# 01_SYSTEM_POWER.net
KiCad netlist of a schematic drawn in Altium Designer
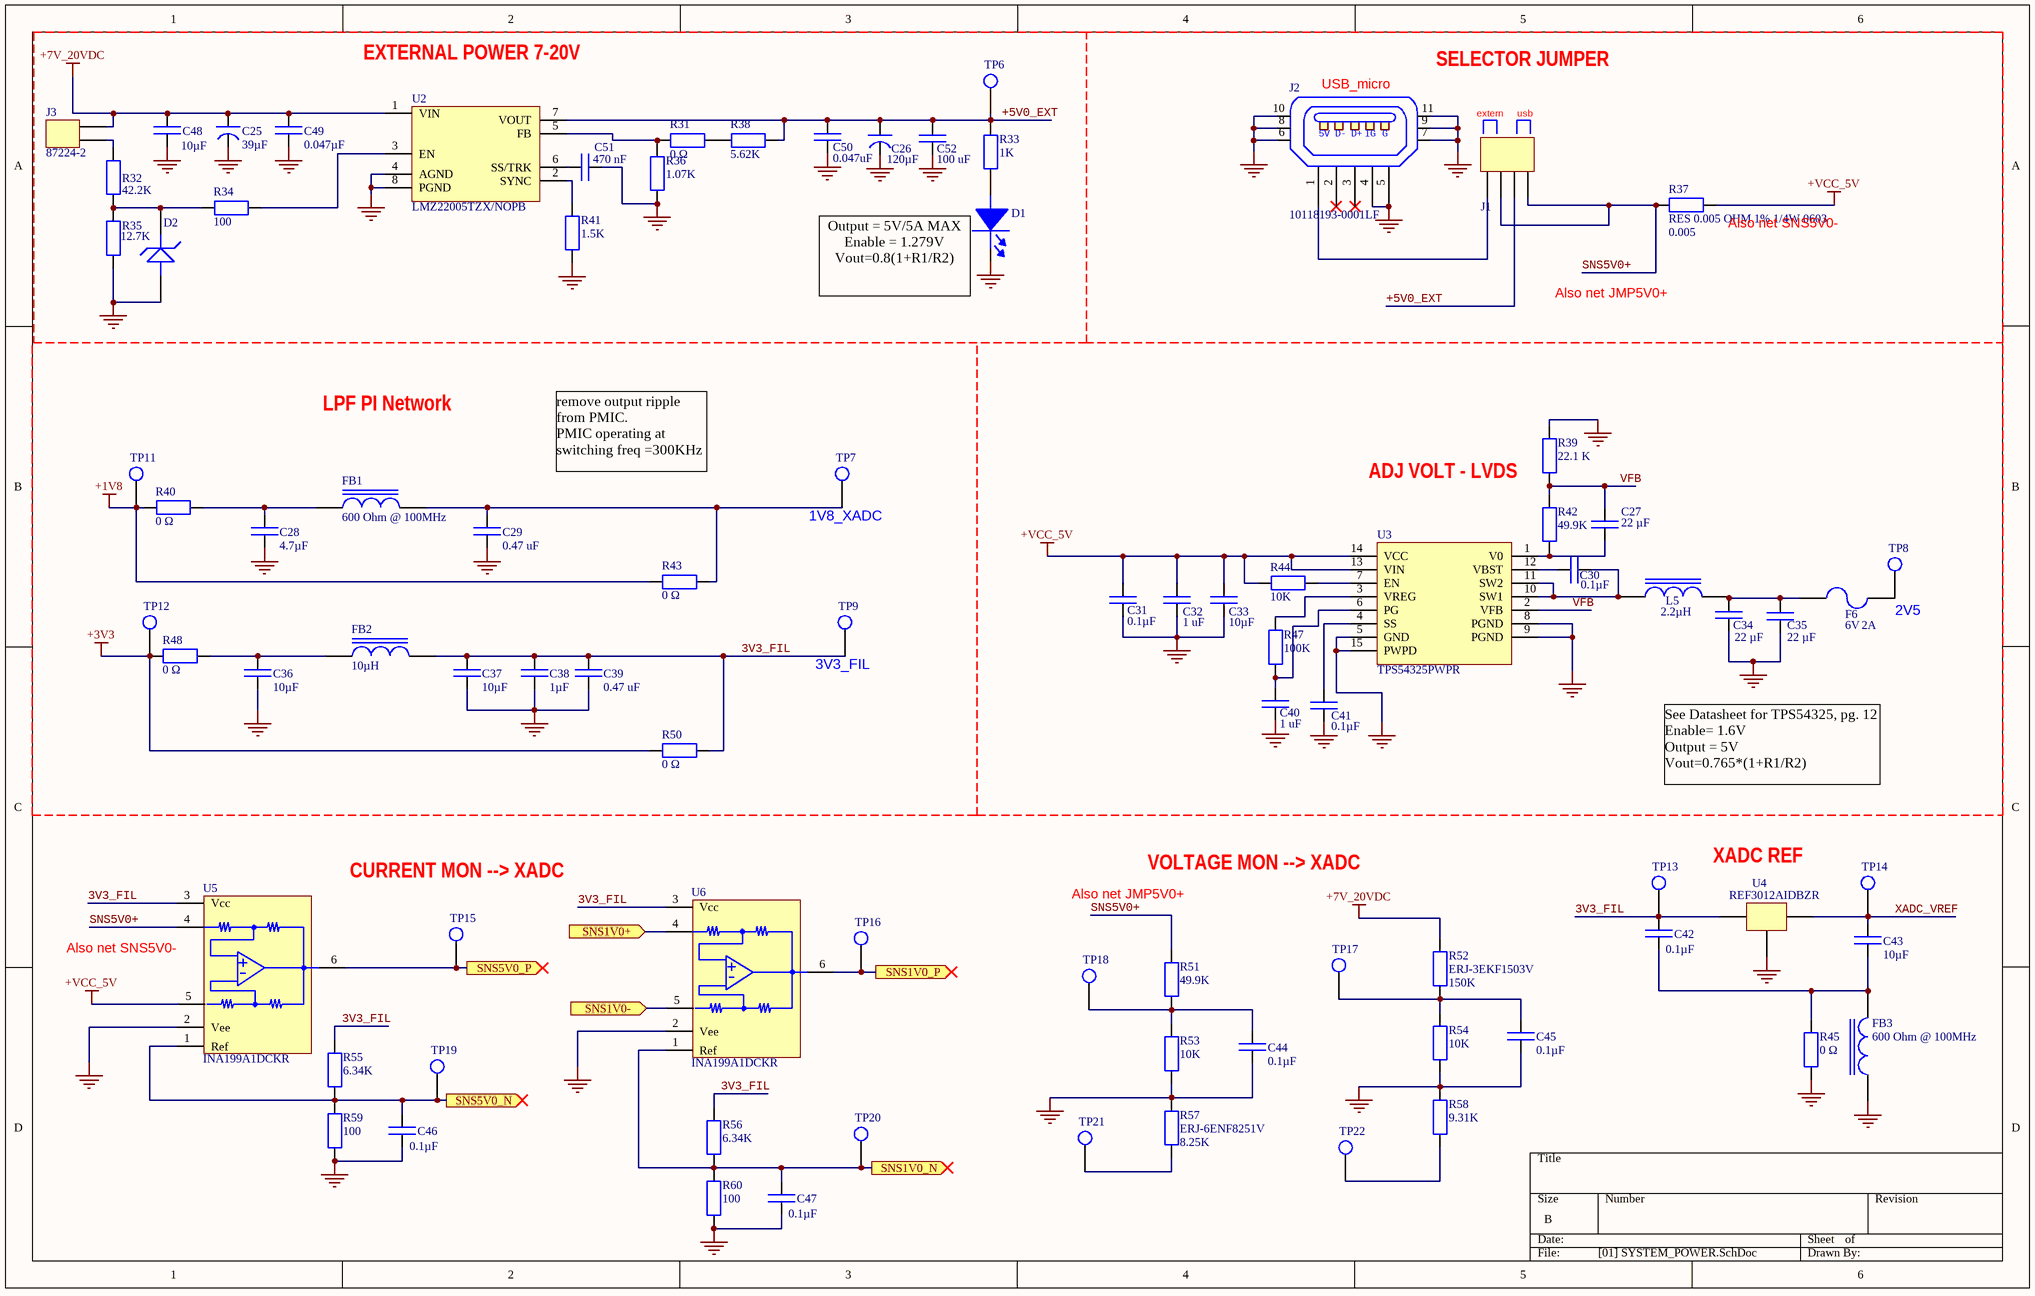
[diagram p0: [01] SYSTEM_POWER.SchDoc]

(export (version "E")
  (design (tool "Eeschema 10.0.6"))
  (components
    (comp (ref "C25")
      (value "35SVPF39M")
      (footprint "Radial E7")
      (description "CAP ALUM POLY 39UF 20% 35V SMD")
      (fields
        (field (name "MANUFACTURER") "Panasonic")
        (field (name "TOLERANCE") "±20%")
        (field (name "CAPACITANCE") "39µF")
      )
      (libsource (lib "Super_Hornet") (part "35SVPF39M"))
    )
    (comp (ref "C26")
      (value "20SVPF120M")
      (footprint "Radial C6")
      (description "CAP ALUM POLY 120UF 20% 20V SMD")
      (fields
        (field (name "MANUFACTURER") "Panasonic")
        (field (name "TOLERANCE") "±20%")
        (field (name "CAPACITANCE") "120µF")
      )
      (libsource (lib "Honey_Badger") (part "20SVPF120M"))
    )
    (comp (ref "C27")
      (value "12063D226KAT2A")
      (footprint "C1206")
      (description "CAP CER 22UF 25V X5R 1206")
      (fields (field (name "MANUFACTURER") "Kyocera AVX") (field (name "CAPACITANCE") "22 µF"))
      (libsource (lib "Honey_Badger") (part "12063D226KAT2A"))
    )
    (comp (ref "C28")
      (value "C2012X5R1C475K060AC")
      (footprint "C0805_1")
      (description "CAP CER 4.7UF 16V X5R 0805")
      (fields
        (field (name "MANUFACTURER") "TDK")
        (field (name "TOLERANCE") "±10%")
        (field (name "CAPACITANCE") "4.7µF")
      )
      (libsource (lib "Honey_Badger") (part "C2012X5R1C475K060AC"))
    )
    (comp (ref "C29")
      (value "GRM188R70J474KA01D")
      (footprint "C0603_1")
      (description "CAP CER 0.47UF 6.3V X7R 0603")
      (fields
        (field (name "MANUFACTURER") "Murata")
        (field (name "TOLERANCE") "10 %")
        (field (name "CAPACITANCE") "0.47 uF")
      )
      (libsource (lib "Honey_Badger") (part "GRM188R70J474KA01D"))
    )
    (comp (ref "C30")
      (value "CC0402KRX7R6BB104")
      (footprint "R0402")
      (description "0402 0.1 uF 10 V ±10 % Tolerance X7R SMT Multilayer Ceramic Capacitor")
      (fields
        (field (name "MANUFACTURER") "Yageo")
        (field (name "TOLERANCE") "±10%")
        (field (name "CAPACITANCE") "0.1µF")
      )
      (libsource (lib "Honey_Badger") (part "CC0402KRX7R6BB104"))
    )
    (comp (ref "C31")
      (value "CC0402KRX7R6BB104")
      (footprint "R0402")
      (description "0402 0.1 uF 10 V ±10 % Tolerance X7R SMT Multilayer Ceramic Capacitor")
      (fields
        (field (name "MANUFACTURER") "Yageo")
        (field (name "TOLERANCE") "±10%")
        (field (name "CAPACITANCE") "0.1µF")
      )
      (libsource (lib "Honey_Badger") (part "CC0402KRX7R6BB104"))
    )
    (comp (ref "C32")
      (value "C0603C105K8RACTU")
      (footprint "C0603_1")
      (description "CAP CER 1UF 10V X7R 0603")
      (fields
        (field (name "MANUFACTURER") "KEMET")
        (field (name "TOLERANCE") "10 %")
        (field (name "CAPACITANCE") "1 uF")
      )
      (libsource (lib "Honey_Badger") (part "C0603C105K8RACTU"))
    )
    (comp (ref "C33")
      (value "C3216X5R1C106M160AA")
      (footprint "C1206")
      (description "CAP CER 10UF 16V X5R 1206")
      (fields
        (field (name "MANUFACTURER") "TDK")
        (field (name "PCN PART NUMBER") "MLCC Part Number Change 30/Nov/2012")
        (field (name "CAPACITANCE") "10µF")
      )
      (libsource (lib "Honey_Badger") (part "C3216X5R1C106M160AA"))
    )
    (comp (ref "C34")
      (value "12063D226KAT2A")
      (footprint "C1206")
      (description "CAP CER 22UF 25V X5R 1206")
      (fields (field (name "MANUFACTURER") "Kyocera AVX") (field (name "CAPACITANCE") "22 µF"))
      (libsource (lib "Honey_Badger") (part "12063D226KAT2A"))
    )
    (comp (ref "C35")
      (value "12063D226KAT2A")
      (footprint "C1206")
      (description "CAP CER 22UF 25V X5R 1206")
      (fields (field (name "MANUFACTURER") "Kyocera AVX") (field (name "CAPACITANCE") "22 µF"))
      (libsource (lib "Honey_Badger") (part "12063D226KAT2A"))
    )
    (comp (ref "C36")
      (value "C3216X5R1C106M160AA")
      (footprint "C1206")
      (description "CAP CER 10UF 16V X5R 1206")
      (fields
        (field (name "MANUFACTURER") "TDK")
        (field (name "PCN PART NUMBER") "MLCC Part Number Change 30/Nov/2012")
        (field (name "CAPACITANCE") "10µF")
      )
      (libsource (lib "Honey_Badger") (part "C3216X5R1C106M160AA"))
    )
    (comp (ref "C37")
      (value "C3216X5R1C106M160AA")
      (footprint "C1206")
      (description "CAP CER 10UF 16V X5R 1206")
      (fields
        (field (name "MANUFACTURER") "TDK")
        (field (name "PCN PART NUMBER") "MLCC Part Number Change 30/Nov/2012")
        (field (name "CAPACITANCE") "10µF")
      )
      (libsource (lib "Honey_Badger") (part "C3216X5R1C106M160AA"))
    )
    (comp (ref "C38")
      (value "C3216X7R1H105K160AE")
      (footprint "C1206")
      (description "CAP CER 1UF 50V X7R 1206")
      (fields
        (field (name "MANUFACTURER") "TDK")
        (field (name "PCN PART NUMBER") "MLCC Part Number Change 30/Nov/2012")
        (field (name "CAPACITANCE") "1µF")
      )
      (libsource (lib "Honey_Badger") (part "C3216X7R1H105K160AE"))
    )
    (comp (ref "C39")
      (value "GRM188R70J474KA01D")
      (footprint "C0603_1")
      (description "CAP CER 0.47UF 6.3V X7R 0603")
      (fields
        (field (name "MANUFACTURER") "Murata")
        (field (name "TOLERANCE") "10 %")
        (field (name "CAPACITANCE") "0.47 uF")
      )
      (libsource (lib "Honey_Badger") (part "GRM188R70J474KA01D"))
    )
    (comp (ref "C40")
      (value "C0603C105K8RACTU")
      (footprint "C0603_1")
      (description "CAP CER 1UF 10V X7R 0603")
      (fields
        (field (name "MANUFACTURER") "KEMET")
        (field (name "TOLERANCE") "10 %")
        (field (name "CAPACITANCE") "1 uF")
      )
      (libsource (lib "Honey_Badger") (part "C0603C105K8RACTU"))
    )
    (comp (ref "C41")
      (value "CC0402KRX7R6BB104")
      (footprint "R0402")
      (description "0402 0.1 uF 10 V ±10 % Tolerance X7R SMT Multilayer Ceramic Capacitor")
      (fields
        (field (name "MANUFACTURER") "Yageo")
        (field (name "TOLERANCE") "±10%")
        (field (name "CAPACITANCE") "0.1µF")
      )
      (libsource (lib "Honey_Badger") (part "CC0402KRX7R6BB104"))
    )
    (comp (ref "C42")
      (value "CC0402KRX7R6BB104")
      (footprint "R0402")
      (description "CAP CER 0.1UF 10V X7R 0402")
      (fields
        (field (name "MANUFACTURER") "Yageo")
        (field (name "TOLERANCE") "±10%")
        (field (name "CAPACITANCE") "0.1µF")
      )
      (libsource (lib "Honey_Badger") (part "CC0402KRX7R6BB104"))
    )
    (comp (ref "C43")
      (value "C3216X5R1C106M160AA")
      (footprint "C1206")
      (description "CAP CER 10UF 16V X5R 1206")
      (fields
        (field (name "MANUFACTURER") "TDK")
        (field (name "PCN PART NUMBER") "MLCC Part Number Change 30/Nov/2012")
        (field (name "CAPACITANCE") "10µF")
      )
      (libsource (lib "Honey_Badger") (part "C3216X5R1C106M160AA"))
    )
    (comp (ref "C44")
      (value "CC0402KRX7R6BB104")
      (footprint "R0402")
      (description "CAP CER 0.1UF 10V X7R 0402")
      (fields
        (field (name "MANUFACTURER") "Yageo")
        (field (name "TOLERANCE") "±10%")
        (field (name "CAPACITANCE") "0.1µF")
      )
      (libsource (lib "Honey_Badger") (part "CC0402KRX7R6BB104"))
    )
    (comp (ref "C45")
      (value "CC0402KRX7R6BB104")
      (footprint "R0402")
      (description "CAP CER 0.1UF 10V X7R 0402")
      (fields
        (field (name "MANUFACTURER") "Yageo")
        (field (name "TOLERANCE") "±10%")
        (field (name "CAPACITANCE") "0.1µF")
      )
      (libsource (lib "Honey_Badger") (part "CC0402KRX7R6BB104"))
    )
    (comp (ref "C46")
      (value "CC0402KRX7R6BB104")
      (footprint "R0402")
      (description "CAP CER 0.1UF 10V X7R 0402")
      (fields
        (field (name "MANUFACTURER") "Yageo")
        (field (name "TOLERANCE") "±10%")
        (field (name "CAPACITANCE") "0.1µF")
      )
      (libsource (lib "Honey_Badger") (part "CC0402KRX7R6BB104"))
    )
    (comp (ref "C47")
      (value "CC0402KRX7R6BB104")
      (footprint "R0402")
      (description "CAP CER 0.1UF 10V X7R 0402")
      (fields
        (field (name "MANUFACTURER") "Yageo")
        (field (name "TOLERANCE") "±10%")
        (field (name "CAPACITANCE") "0.1µF")
      )
      (libsource (lib "Honey_Badger") (part "CC0402KRX7R6BB104"))
    )
    (comp (ref "C48")
      (value "GRM188R6YA106MA73D")
      (footprint "C0603_1")
      (description "CAP CER 10UF 35V X5R 0603")
      (fields
        (field (name "MANUFACTURER") "Murata")
        (field (name "CAPACITANCE") "10µF")
        (field (name "TOLERANCE") "±20%")
      )
      (libsource (lib "Super_Hornet") (part "GRM188R6YA106MA73D"))
    )
    (comp (ref "C49")
      (value "GMK107BJ473KAHT")
      (footprint "C0603_1")
      (description "CAP CER 0.047UF 35V X5R 0603")
      (fields
        (field (name "MANUFACTURER") "Taiyo Yuden")
        (field (name "TOLERANCE") "±10%")
        (field (name "MINIMUM QUANTITY") "0.047µF")
      )
      (libsource (lib "Super_Hornet") (part "GMK107BJ473KAHT"))
    )
    (comp (ref "C50")
      (value "C0603C473K8RAC7867")
      (footprint "R0603")
      (description "CAP CER 0.047UF 10V X7R 0603")
      (fields
        (field (name "MANUFACTURER") "KEMET")
        (field (name "VOLTAGE") "10 Vdc")
        (field (name "CAPACITANCE VALUE") "0.047uF")
      )
      (libsource (lib "Super_Hornet") (part "C0603C473K8RAC7867"))
    )
    (comp (ref "C51")
      (value "0805YC474KAT2A")
      (footprint "C0805_1")
      (description "CAP CER 0.47UF 16V X7R 0805")
      (fields (field (name "MANUFACTURER") "Kyocera AVX") (field (name "CAPACITANCE") "470 nF"))
      (libsource (lib "Super_Hornet") (part "0805YC474KAT2A"))
    )
    (comp (ref "C52")
      (value "GRM31CR60J107ME39K")
      (footprint "C1206")
      (description "CAP CER 100UF 6.3V X5R 1206")
      (fields
        (field (name "MANUFACTURER") "Murata")
        (field (name "VOLTAGE") "6.3 Vdc")
        (field (name "CAPACITANCE VALUE") "100 uF")
      )
      (libsource (lib "Super_Hornet") (part "GRM31CR60J107ME39K"))
    )
    (comp (ref "D1")
      (value "SML-LXFP0603USBCTR")
      (footprint "LED-0603-BLUE")
      (description "LED BLUE CLEAR 0603 SMD")
      (fields (field (name "MANUFACTURER") "Lumex"))
      (libsource (lib "Honey_Badger") (part "SML-LXFP0603USBCTR"))
    )
    (comp (ref "D2")
      (value "MMSZ5231BS-7-F")
      (footprint "SOD-323_R1")
      (description "DIODE ZENER 5.1V 200MW SOD323")
      (fields (field (name "MANUFACTURER") "Diodes"))
      (libsource (lib "Super_Hornet") (part "MMSZ5231BS-7-F"))
    )
    (comp (ref "F6")
      (value "MF-NSML200-2")
      (footprint "C1206 - PTC")
      (description "PTC FUSE 2A HOLD 4ATRIP 6V 50A 0.8W 1s")
      (fields
        (field (name "MANUFACTURER") "Bourns")
        (field (name "VOLTAGE - MAX") "6V")
        (field (name "CURRENT - HOLD (IH) (MAX)") "2A")
      )
      (libsource (lib "Honey_Badger") (part "MF-NSML200-2"))
    )
    (comp (ref "FB1")
      (value "FERRITE BEAD 600 OHM 0805 1LN")
      (footprint "R0805")
      (fields
        (field (name "MANUFACTURER") "Laird")
        (field (name "MANUFACTURER PART NUMBER") "HZ0805E601R-10")
        (field (name "IMPEDANCE @ FREQUENCY") "600 Ohm @ 100MHz")
      )
      (libsource (lib "Honey_Badger") (part "HZ0805E601R-10"))
    )
    (comp (ref "FB2")
      (value "MLZ2012N100LT000")
      (footprint "R0805")
      (description "IND 10UH 500MA 300 MOHM")
      (fields
        (field (name "MANUFACTURER") "TDK")
        (field (name "TOLERANCE") "±20%")
        (field (name "INDUCTANCE") "10µH")
      )
      (libsource (lib "Honey_Badger") (part "MLZ2012N100LT000"))
    )
    (comp (ref "FB3")
      (value "FERRITE BEAD 600 OHM 0805 1LN")
      (footprint "R0805")
      (fields
        (field (name "MANUFACTURER") "Laird")
        (field (name "MANUFACTURER PART NUMBER") "HZ0805E601R-10")
        (field (name "IMPEDANCE @ FREQUENCY") "600 Ohm @ 100MHz")
      )
      (libsource (lib "Honey_Badger") (part "HZ0805E601R-10"))
    )
    (comp (ref "J1")
      (value "PRPC004SAAN-RC")
      (footprint "HDR_MALE_1x4_2.54mm")
      (description "CONN HEADER VERT 4POS 2.54MM")
      (fields (field (name "MANUFACTURER") "Sullins"))
      (libsource (lib "Super_Hornet") (part "PRPC004SAAN-RC"))
    )
    (comp (ref "J2")
      (value "10118193-0001LF")
      (footprint "USB_MICRO - duplicate")
      (description "USB - micro B USB 2.0 Receptacle Connector 5 Position Surface Mount, Right Angle, Horizontal")
      (fields (field (name "MANUFACTURER") "Amphenol FCI"))
      (libsource (lib "Super_Hornet") (part "10118193-0001LF_1"))
    )
    (comp (ref "J3")
      (value "87224-2")
      (footprint "HDR_MALE_1x2_2.54mm")
      (description "CONN HEADER VERT 2POS 2.54MM")
      (fields (field (name "MANUFACTURER") "TE Connectivity"))
      (libsource (lib "Super_Hornet") (part "87224-2"))
    )
    (comp (ref "L5")
      (value "SPM10040T-2R2M")
      (footprint "2.2UH_10_7MMx10.4MM")
      (description "IND 2.2UH 12A 7.5MOHM")
      (fields
        (field (name "MANUFACTURER") "TDK")
        (field (name "TOLERANCE") "±20%")
        (field (name "INDUCTANCE") "2.2µH")
      )
      (libsource (lib "Honey_Badger") (part "SPM10040T-2R2M"))
    )
    (comp (ref "R31")
      (value "ERJ-6GEY0R00V")
      (footprint "R0805")
      (description "RES SMD 0 OHM JUMPER 1/8W 0805")
      (fields (field (name "MANUFACTURER") "Panasonic") (field (name "RESISTANCE") "0 Ω"))
      (libsource (lib "Super_Hornet") (part "ERJ-6GEY0R00V"))
    )
    (comp (ref "R32")
      (value "ERJ-3EKF4222V")
      (footprint "R0603")
      (description "RES SMD 42.2K OHM 1% 1/10W 0603")
      (fields
        (field (name "MANUFACTURER") "Panasonic")
        (field (name "RESISTANCE (OHMS)") "42.2K")
        (field (name "TOLERANCE") "±1%")
      )
      (libsource (lib "Super_Hornet") (part "ERJ-3EKF4222V"))
    )
    (comp (ref "R33")
      (value "ERA-3AEB102V")
      (footprint "R0603")
      (description "RES SMD 1K OHM 0.1% 1/10W 0603")
      (fields (field (name "MANUFACTURER") "Panasonic") (field (name "RESISTANCE") "1K"))
      (libsource (lib "Super_Hornet") (part "ERA-3AEB102V"))
    )
    (comp (ref "R34")
      (value "ERJ3EKF1000V")
      (footprint "R0603")
      (description "RES SMD 100 OHM 1% 1/10W 0603")
      (fields (field (name "MANUFACTURER") "Panasonic") (field (name "RESISTANCE") "100"))
      (libsource (lib "Super_Hornet") (part "ERJ3EKF1000V"))
    )
    (comp (ref "R35")
      (value "ERJ-3EKF1272V")
      (footprint "R0603")
      (description "RES SMD 12.7K OHM 1% 1/10W 0603")
      (fields (field (name "MANUFACTURER") "Panasonic") (field (name "RESISTANCE") "12.7K"))
      (libsource (lib "Super_Hornet") (part "ERJ-3EKF1272V"))
    )
    (comp (ref "R36")
      (value "ERJ-6ENF1071V")
      (footprint "R0805")
      (description "RES SMD 1.07K OHM 1% 1/8W 0805")
      (fields
        (field (name "MANUFACTURER") "Panasonic")
        (field (name "TOLERANCE") "±1%")
        (field (name "RESISTANCE (OHMS)") "1.07K")
      )
      (libsource (lib "Super_Hornet") (part "ERJ-6ENF1071V"))
    )
    (comp (ref "R37")
      (value "RES 0.005 OHM 1% 1/4W 0603")
      (footprint "R0603")
      (fields
        (field (name "MANUFACTURER") "Panasonic")
        (field (name "MANUFACTURER PART NUMBER") "ERJ-3LWFR005V")
        (field (name "TOLERANCE") "±1%")
        (field (name "RESISTANCE (OHMS)") "0.005")
      )
      (libsource (lib "Super_Hornet") (part "ERJ-3LWFR005V"))
    )
    (comp (ref "R38")
      (value "ERJ-6ENF5621V")
      (footprint "R0805")
      (description "RES SMD 5.62K OHM 1% 1/8W 0805")
      (fields (field (name "MANUFACTURER") "Panasonic") (field (name "RESISTANCE") "5.62K"))
      (libsource (lib "Super_Hornet") (part "ERJ-6ENF5621V"))
    )
    (comp (ref "R39")
      (value "ERJ-3EKF2212V")
      (footprint "R0603")
      (description "RES SMD 22.1K OHM 1% 1/10W 0603")
      (fields (field (name "MANUFACTURER") "Panasonic") (field (name "RESISTANCE") "22.1 K"))
      (libsource (lib "Super_Hornet") (part "ERJ-3EKF2212V"))
    )
    (comp (ref "R40")
      (value "ERJ-6GEY0R00V")
      (footprint "R0805")
      (description "RES SMD 0 OHM JUMPER 1/8W 0805")
      (fields (field (name "MANUFACTURER") "Panasonic") (field (name "RESISTANCE") "0 Ω"))
      (libsource (lib "Super_Hornet") (part "ERJ-6GEY0R00V"))
    )
    (comp (ref "R41")
      (value "ERJ-3EKF1501V")
      (footprint "R0603")
      (description "RES SMD 1.5K OHM ±1% 1/10W 0603")
      (fields
        (field (name "MANUFACTURER") "Panasonic")
        (field (name "TOLERANCE") "1 %")
        (field (name "RESISTANCE") "1.5K")
      )
      (libsource (lib "Super_Hornet") (part "ERJ-3EKF1501V"))
    )
    (comp (ref "R42")
      (value "ERJ-3EKF4992V")
      (footprint "R0603")
      (description "RES SMD 49.9K OHM 1% 1/10W 0603")
      (fields (field (name "MANUFACTURER") "Panasonic") (field (name "RESISTANCE") "49.9K"))
      (libsource (lib "Super_Hornet") (part "ERJ-3EKF4992V"))
    )
    (comp (ref "R43")
      (value "ERJ-6GEY0R00V")
      (footprint "R0805")
      (description "RES SMD 0 OHM JUMPER 1/8W 0805")
      (fields (field (name "MANUFACTURER") "Panasonic") (field (name "RESISTANCE") "0 Ω"))
      (libsource (lib "Super_Hornet") (part "ERJ-6GEY0R00V"))
    )
    (comp (ref "R44")
      (value "ERJ-3EKF1002V")
      (footprint "R0603")
      (description "RES SMD 10K OHM 1% 1/10W 0603")
      (fields (field (name "MANUFACTURER") "Panasonic") (field (name "RESISTANCE") "10K"))
      (libsource (lib "Super_Hornet") (part "ERJ-3EKF1002V"))
    )
    (comp (ref "R45")
      (value "ERJ-6GEY0R00V")
      (footprint "R0805")
      (description "RES SMD 0 OHM JUMPER 1/8W 0805")
      (fields (field (name "MANUFACTURER") "Panasonic") (field (name "RESISTANCE") "0 Ω"))
      (libsource (lib "Super_Hornet") (part "ERJ-6GEY0R00V"))
    )
    (comp (ref "R47")
      (value "ERJ3EKF1003V")
      (footprint "R0603")
      (description "RES SMD 100K OHM 1% 1/10W 0603")
      (fields (field (name "MANUFACTURER") "Panasonic") (field (name "RESISTANCE") "100K"))
      (libsource (lib "Super_Hornet") (part "ERJ3EKF1003V"))
    )
    (comp (ref "R48")
      (value "ERJ-6GEY0R00V")
      (footprint "R0805")
      (description "RES SMD 0 OHM JUMPER 1/8W 0805")
      (fields (field (name "MANUFACTURER") "Panasonic") (field (name "RESISTANCE") "0 Ω"))
      (libsource (lib "Super_Hornet") (part "ERJ-6GEY0R00V"))
    )
    (comp (ref "R50")
      (value "ERJ-6GEY0R00V")
      (footprint "R0805")
      (description "RES SMD 0 OHM JUMPER 1/8W 0805")
      (fields (field (name "MANUFACTURER") "Panasonic") (field (name "RESISTANCE") "0 Ω"))
      (libsource (lib "Super_Hornet") (part "ERJ-6GEY0R00V"))
    )
    (comp (ref "R51")
      (value "ERJ-3EKF4992V")
      (footprint "R0603")
      (description "RES SMD 49.9K OHM 1% 1/10W 0603")
      (fields (field (name "MANUFACTURER") "Panasonic") (field (name "RESISTANCE") "49.9K"))
      (libsource (lib "Super_Hornet") (part "ERJ-3EKF4992V"))
    )
    (comp (ref "R52")
      (value "ERJ-3EKF1503V")
      (footprint "R0603")
      (description "RES SMD 150K OHM 1% 1/10W 0603")
      (fields
        (field (name "MANUFACTURER") "Panasonic")
        (field (name "TOLERANCE") "1 %")
        (field (name "RESISTANCE VALUE") "150K")
      )
      (libsource (lib "Super_Hornet") (part "ERJ-3EKF1503V"))
    )
    (comp (ref "R53")
      (value "ERJ-3EKF1002V")
      (footprint "R0603")
      (description "RES SMD 10K OHM 1% 1/10W 0603")
      (fields (field (name "MANUFACTURER") "Panasonic") (field (name "RESISTANCE") "10K"))
      (libsource (lib "Super_Hornet") (part "ERJ-3EKF1002V"))
    )
    (comp (ref "R54")
      (value "ERJ-3EKF1002V")
      (footprint "R0603")
      (description "RES SMD 10K OHM 1% 1/10W 0603")
      (fields (field (name "MANUFACTURER") "Panasonic") (field (name "RESISTANCE") "10K"))
      (libsource (lib "Super_Hornet") (part "ERJ-3EKF1002V"))
    )
    (comp (ref "R55")
      (value "ERJ-3EKF6341V")
      (footprint "R0603")
      (description "RES SMD 6.34K OHM 1% 1/10W 0603")
      (fields (field (name "MANUFACTURER") "Panasonic") (field (name "RESISTANCE") "6.34K"))
      (libsource (lib "Super_Hornet") (part "ERJ-3EKF6341V"))
    )
    (comp (ref "R56")
      (value "ERJ-3EKF6341V")
      (footprint "R0603")
      (description "RES SMD 6.34K OHM 1% 1/10W 0603")
      (fields (field (name "MANUFACTURER") "Panasonic") (field (name "RESISTANCE") "6.34K"))
      (libsource (lib "Super_Hornet") (part "ERJ-3EKF6341V"))
    )
    (comp (ref "R57")
      (value "ERJ-6ENF8251V")
      (footprint "R0805")
      (description "RES SMD 8.25K OHM 1% 1/8W 0805")
      (fields (field (name "MANUFACTURER") "Panasonic") (field (name "RESISTANCE") "8.25K"))
      (libsource (lib "Super_Hornet") (part "ERJ-6ENF8251V"))
    )
    (comp (ref "R58")
      (value "ERJ-3EKF9311V")
      (footprint "R0603")
      (description "RES SMD 9.31K OHM 1% 1/10W 0603")
      (fields (field (name "MANUFACTURER") "Panasonic") (field (name "RESISTANCE") "9.31K"))
      (libsource (lib "Super_Hornet") (part "ERJ-3EKF9311V"))
    )
    (comp (ref "R59")
      (value "ERJ3EKF1000V")
      (footprint "R0603")
      (description "RES SMD 100 OHM 1% 1/10W 0603")
      (fields (field (name "MANUFACTURER") "Panasonic") (field (name "RESISTANCE") "100"))
      (libsource (lib "Super_Hornet") (part "ERJ3EKF1000V"))
    )
    (comp (ref "R60")
      (value "ERJ3EKF1000V")
      (footprint "R0603")
      (description "RES SMD 100 OHM 1% 1/10W 0603")
      (fields (field (name "MANUFACTURER") "Panasonic") (field (name "RESISTANCE") "100"))
      (libsource (lib "Super_Hornet") (part "ERJ3EKF1000V"))
    )
    (comp (ref "TP6")
      (value "5017")
      (footprint "TEST_POINT")
      (description "PCB MINI TEST POINT")
      (fields (field (name "MANUFACTURER") "Keystone Electronics"))
      (libsource (lib "Super_Hornet") (part "5017"))
    )
    (comp (ref "TP7")
      (value "5017")
      (footprint "TEST_POINT")
      (description "PCB MINI TEST POINT")
      (fields (field (name "MANUFACTURER") "Keystone Electronics"))
      (libsource (lib "Super_Hornet") (part "5017"))
    )
    (comp (ref "TP8")
      (value "5017")
      (footprint "TEST_POINT")
      (description "PCB MINI TEST POINT")
      (fields (field (name "MANUFACTURER") "Keystone Electronics"))
      (libsource (lib "Super_Hornet") (part "5017"))
    )
    (comp (ref "TP9")
      (value "5017")
      (footprint "TEST_POINT")
      (description "PCB MINI TEST POINT")
      (fields (field (name "MANUFACTURER") "Keystone Electronics"))
      (libsource (lib "Super_Hornet") (part "5017"))
    )
    (comp (ref "TP11")
      (value "5017")
      (footprint "TEST_POINT")
      (description "PCB MINI TEST POINT")
      (fields (field (name "MANUFACTURER") "Keystone Electronics"))
      (libsource (lib "Super_Hornet") (part "5017"))
    )
    (comp (ref "TP12")
      (value "5017")
      (footprint "TEST_POINT")
      (description "PCB MINI TEST POINT")
      (fields (field (name "MANUFACTURER") "Keystone Electronics"))
      (libsource (lib "Super_Hornet") (part "5017"))
    )
    (comp (ref "TP13")
      (value "5017")
      (footprint "TEST_POINT")
      (description "PCB MINI TEST POINT")
      (fields (field (name "MANUFACTURER") "Keystone Electronics"))
      (libsource (lib "Super_Hornet") (part "5017"))
    )
    (comp (ref "TP14")
      (value "5017")
      (footprint "TEST_POINT")
      (description "PCB MINI TEST POINT")
      (fields (field (name "MANUFACTURER") "Keystone Electronics"))
      (libsource (lib "Super_Hornet") (part "5017"))
    )
    (comp (ref "TP15")
      (value "5017")
      (footprint "TEST_POINT")
      (description "PCB MINI TEST POINT")
      (fields (field (name "MANUFACTURER") "Keystone Electronics"))
      (libsource (lib "Super_Hornet") (part "5017"))
    )
    (comp (ref "TP16")
      (value "5017")
      (footprint "TEST_POINT")
      (description "PCB MINI TEST POINT")
      (fields (field (name "MANUFACTURER") "Keystone Electronics"))
      (libsource (lib "Super_Hornet") (part "5017"))
    )
    (comp (ref "TP17")
      (value "5017")
      (footprint "TEST_POINT")
      (description "PCB MINI TEST POINT")
      (fields (field (name "MANUFACTURER") "Keystone Electronics"))
      (libsource (lib "Super_Hornet") (part "5017"))
    )
    (comp (ref "TP18")
      (value "5017")
      (footprint "TEST_POINT")
      (description "PCB MINI TEST POINT")
      (fields (field (name "MANUFACTURER") "Keystone Electronics"))
      (libsource (lib "Super_Hornet") (part "5017"))
    )
    (comp (ref "TP19")
      (value "5017")
      (footprint "TEST_POINT")
      (description "PCB MINI TEST POINT")
      (fields (field (name "MANUFACTURER") "Keystone Electronics"))
      (libsource (lib "Super_Hornet") (part "5017"))
    )
    (comp (ref "TP20")
      (value "5017")
      (footprint "TEST_POINT")
      (description "PCB MINI TEST POINT")
      (fields (field (name "MANUFACTURER") "Keystone Electronics"))
      (libsource (lib "Super_Hornet") (part "5017"))
    )
    (comp (ref "TP21")
      (value "5017")
      (footprint "TEST_POINT")
      (description "PCB MINI TEST POINT")
      (fields (field (name "MANUFACTURER") "Keystone Electronics"))
      (libsource (lib "Super_Hornet") (part "5017"))
    )
    (comp (ref "TP22")
      (value "5017")
      (footprint "TEST_POINT")
      (description "PCB MINI TEST POINT")
      (fields (field (name "MANUFACTURER") "Keystone Electronics"))
      (libsource (lib "Super_Hornet") (part "5017"))
    )
    (comp (ref "U2")
      (value "LMZ22005TZX/NOPB")
      (footprint "TO-PMOD-7")
      (description "DC DC CONVERTER 0.8-6V")
      (fields
        (field (name "MANUFACTURER") "TI National Semiconductor")
        (field (name "MANUFACTURER PART NUMBER") "LMZ22005TZX/NOPB")
      )
      (libsource (lib "Honey_Badger") (part "LMZ22005TZX/NOPB"))
    )
    (comp (ref "U3")
      (value "TPS54325PWPR")
      (footprint "14-HTSSOP")
      (description "IC REG BUCK ADJ 3A SYNC 14HTSSOP")
      (fields (field (name "MANUFACTURER") "Texas Instruments"))
      (libsource (lib "Honey_Badger") (part "TPS54325PWPR"))
    )
    (comp (ref "U4")
      (value "REF3012AIDBZR")
      (footprint "SOT-23-3")
      (description "IC VREF SERIES 0.2% SOT23-3")
      (fields
        (field (name "MANUFACTURER") "Texas Instruments")
        (field (name "MANUFACTURER PART NUMBER") "REF3012AIDBZR")
      )
      (libsource (lib "Honey_Badger") (part "REF3012AIDBZR"))
    )
    (comp (ref "U5")
      (value "INA199A1DCKR")
      (footprint "SOT-363")
      (description "IC OPAMP CURR SENSE 14KHZ SC70-6")
      (fields
        (field (name "MANUFACTURER") "Texas Instruments")
        (field (name "MANUFACTURER PART NUMBER") "INA199A1DCKR")
      )
      (libsource (lib "Super_Hornet") (part "INA199A1DCKR"))
    )
    (comp (ref "U6")
      (value "INA199A1DCKR")
      (footprint "SOT-363")
      (description "IC OPAMP CURR SENSE 14KHZ SC70-6")
      (fields
        (field (name "MANUFACTURER") "Texas Instruments")
        (field (name "MANUFACTURER PART NUMBER") "INA199A1DCKR")
      )
      (libsource (lib "Super_Hornet") (part "INA199A1DCKR"))
    )
  )
  (nets
    (net (code "1") (name "+1V8") (class "Default")
      (node (ref "R40") (pin "2") (pinfunction "2_2") (pintype "passive"))
      (node (ref "R43") (pin "2") (pinfunction "2_2") (pintype "passive"))
      (node (ref "TP11") (pin "1") (pinfunction "1_1") (pintype "passive"))
    )
    (net (code "2") (name "+3V3") (class "Default")
      (node (ref "R48") (pin "2") (pinfunction "2_2") (pintype "passive"))
      (node (ref "R50") (pin "2") (pinfunction "2_2") (pintype "passive"))
      (node (ref "TP12") (pin "1") (pinfunction "1_1") (pintype "passive"))
    )
    (net (code "3") (name "+7V_20VDC") (class "Default")
      (node (ref "C25") (pin "1") (pinfunction "1_1") (pintype "passive"))
      (node (ref "C48") (pin "2") (pinfunction "2_2") (pintype "passive"))
      (node (ref "C49") (pin "2") (pinfunction "2_2") (pintype "passive"))
      (node (ref "J3") (pin "2") (pinfunction "2_2") (pintype "passive"))
      (node (ref "R52") (pin "2") (pinfunction "2_2") (pintype "passive"))
      (node (ref "U2") (pin "1") (pinfunction "VIN_1") (pintype "passive"))
    )
    (net (code "4") (name "+VCC_5V") (class "Default")
      (node (ref "C31") (pin "1") (pinfunction "1_1") (pintype "passive"))
      (node (ref "C32") (pin "2") (pinfunction "2_2") (pintype "passive"))
      (node (ref "C33") (pin "2") (pinfunction "2_2") (pintype "passive"))
      (node (ref "R37") (pin "2") (pinfunction "2_2") (pintype "passive"))
      (node (ref "R44") (pin "1") (pinfunction "1_1") (pintype "passive"))
      (node (ref "U3") (pin "13") (pinfunction "VIN_13") (pintype "passive"))
      (node (ref "U3") (pin "14") (pinfunction "VCC_14") (pintype "passive"))
      (node (ref "U5") (pin "5") (pinfunction "-_5") (pintype "passive"))
    )
    (net (code "5") (name "/+5V0_EXT") (class "Default")
      (node (ref "C26") (pin "1") (pinfunction "1_1") (pintype "passive"))
      (node (ref "C50") (pin "2") (pinfunction "2_2") (pintype "passive"))
      (node (ref "C52") (pin "2") (pinfunction "2_2") (pintype "passive"))
      (node (ref "J1") (pin "3") (pinfunction "3_3") (pintype "passive"))
      (node (ref "R33") (pin "2") (pinfunction "2_2") (pintype "passive"))
      (node (ref "R38") (pin "2") (pinfunction "2_2") (pintype "passive"))
      (node (ref "TP6") (pin "1") (pinfunction "1_1") (pintype "passive"))
      (node (ref "U2") (pin "7") (pinfunction "VOUT_7") (pintype "passive"))
    )
    (net (code "6") (name "/3V3_FIL") (class "Default")
      (node (ref "C37") (pin "2") (pinfunction "2_2") (pintype "passive"))
      (node (ref "C38") (pin "2") (pinfunction "2_2") (pintype "passive"))
      (node (ref "C39") (pin "2") (pinfunction "2_2") (pintype "passive"))
      (node (ref "C42") (pin "2") (pinfunction "2_2") (pintype "passive"))
      (node (ref "FB2") (pin "2") (pinfunction "2_2") (pintype "passive"))
      (node (ref "R50") (pin "1") (pinfunction "1_1") (pintype "passive"))
      (node (ref "R55") (pin "2") (pinfunction "2_2") (pintype "passive"))
      (node (ref "R56") (pin "2") (pinfunction "2_2") (pintype "passive"))
      (node (ref "TP13") (pin "1") (pinfunction "1_1") (pintype "passive"))
      (node (ref "TP9") (pin "1") (pinfunction "1_1") (pintype "passive"))
      (node (ref "U4") (pin "1") (pinfunction "1_1") (pintype "passive"))
      (node (ref "U5") (pin "3") (pinfunction "Vcc_3") (pintype "passive"))
      (node (ref "U6") (pin "3") (pinfunction "Vcc_3") (pintype "passive"))
    )
    (net (code "7") (name "/SNS1V0+") (class "Default")
      (node (ref "U6") (pin "4") (pinfunction "+_4") (pintype "passive"))
    )
    (net (code "8") (name "/SNS1V0-") (class "Default")
      (node (ref "U6") (pin "5") (pinfunction "-_5") (pintype "passive"))
    )
    (net (code "9") (name "/SNS1V0_N") (class "Default")
      (node (ref "C47") (pin "2") (pinfunction "2_2") (pintype "passive"))
      (node (ref "R56") (pin "1") (pinfunction "1_1") (pintype "passive"))
      (node (ref "R60") (pin "2") (pinfunction "2_2") (pintype "passive"))
      (node (ref "TP20") (pin "1") (pinfunction "1_1") (pintype "passive"))
      (node (ref "U6") (pin "1") (pinfunction "Ref_1") (pintype "passive"))
    )
    (net (code "10") (name "/SNS1V0_P") (class "Default")
      (node (ref "TP16") (pin "1") (pinfunction "1_1") (pintype "passive"))
      (node (ref "U6") (pin "6") (pinfunction "OUT_6") (pintype "passive"))
    )
    (net (code "11") (name "/SNS5V0+") (class "Default")
      (node (ref "J1") (pin "2") (pinfunction "2_2") (pintype "passive"))
      (node (ref "J1") (pin "4") (pinfunction "4_4") (pintype "passive"))
      (node (ref "R37") (pin "1") (pinfunction "1_1") (pintype "passive"))
      (node (ref "R51") (pin "2") (pinfunction "2_2") (pintype "passive"))
      (node (ref "U5") (pin "4") (pinfunction "+_4") (pintype "passive"))
    )
    (net (code "12") (name "/SNS5V0_N") (class "Default")
      (node (ref "C46") (pin "2") (pinfunction "2_2") (pintype "passive"))
      (node (ref "R55") (pin "1") (pinfunction "1_1") (pintype "passive"))
      (node (ref "R59") (pin "2") (pinfunction "2_2") (pintype "passive"))
      (node (ref "TP19") (pin "1") (pinfunction "1_1") (pintype "passive"))
      (node (ref "U5") (pin "1") (pinfunction "Ref_1") (pintype "passive"))
    )
    (net (code "13") (name "/SNS5V0_P") (class "Default")
      (node (ref "TP15") (pin "1") (pinfunction "1_1") (pintype "passive"))
      (node (ref "U5") (pin "6") (pinfunction "OUT_6") (pintype "passive"))
    )
    (net (code "14") (name "/VFB") (class "Default")
      (node (ref "C27") (pin "2") (pinfunction "2_2") (pintype "passive"))
      (node (ref "R39") (pin "1") (pinfunction "1_1") (pintype "passive"))
      (node (ref "R42") (pin "2") (pinfunction "2_2") (pintype "passive"))
      (node (ref "U3") (pin "2") (pinfunction "VFB_2") (pintype "passive"))
    )
    (net (code "15") (name "/XADC_VREF") (class "Default")
      (node (ref "C43") (pin "2") (pinfunction "2_2") (pintype "passive"))
      (node (ref "TP14") (pin "1") (pinfunction "1_1") (pintype "passive"))
      (node (ref "U4") (pin "2") (pinfunction "2_2") (pintype "passive"))
    )
    (net (code "16") (name "GND") (class "Default")
      (node (ref "C25") (pin "2") (pinfunction "2_2") (pintype "passive"))
      (node (ref "C26") (pin "2") (pinfunction "2_2") (pintype "passive"))
      (node (ref "C28") (pin "1") (pinfunction "1_1") (pintype "passive"))
      (node (ref "C29") (pin "1") (pinfunction "1_1") (pintype "passive"))
      (node (ref "C31") (pin "2") (pinfunction "2_2") (pintype "passive"))
      (node (ref "C32") (pin "1") (pinfunction "1_1") (pintype "passive"))
      (node (ref "C33") (pin "1") (pinfunction "1_1") (pintype "passive"))
      (node (ref "C34") (pin "1") (pinfunction "1_1") (pintype "passive"))
      (node (ref "C35") (pin "1") (pinfunction "1_1") (pintype "passive"))
      (node (ref "C36") (pin "1") (pinfunction "1_1") (pintype "passive"))
      (node (ref "C37") (pin "1") (pinfunction "1_1") (pintype "passive"))
      (node (ref "C38") (pin "1") (pinfunction "1_1") (pintype "passive"))
      (node (ref "C39") (pin "1") (pinfunction "1_1") (pintype "passive"))
      (node (ref "C40") (pin "1") (pinfunction "1_1") (pintype "passive"))
      (node (ref "C41") (pin "2") (pinfunction "2_2") (pintype "passive"))
      (node (ref "C44") (pin "2") (pinfunction "2_2") (pintype "passive"))
      (node (ref "C45") (pin "2") (pinfunction "2_2") (pintype "passive"))
      (node (ref "C46") (pin "1") (pinfunction "1_1") (pintype "passive"))
      (node (ref "C47") (pin "1") (pinfunction "1_1") (pintype "passive"))
      (node (ref "C48") (pin "1") (pinfunction "1_1") (pintype "passive"))
      (node (ref "C49") (pin "1") (pinfunction "1_1") (pintype "passive"))
      (node (ref "C50") (pin "1") (pinfunction "1_1") (pintype "passive"))
      (node (ref "C51") (pin "1") (pinfunction "1_1") (pintype "passive"))
      (node (ref "C52") (pin "1") (pinfunction "1_1") (pintype "passive"))
      (node (ref "D1") (pin "2") (pinfunction "CATHODE_2") (pintype "passive"))
      (node (ref "D2") (pin "1") (pinfunction "1_1") (pintype "passive"))
      (node (ref "FB3") (pin "1") (pinfunction "1_1") (pintype "passive"))
      (node (ref "J2") (pin "10") (pinfunction "10_10") (pintype "passive"))
      (node (ref "J2") (pin "11") (pinfunction "11_11") (pintype "passive"))
      (node (ref "J2") (pin "4") (pinfunction "4_4") (pintype "passive"))
      (node (ref "J2") (pin "5") (pinfunction "5_5") (pintype "passive"))
      (node (ref "J2") (pin "6") (pinfunction "6_6") (pintype "passive"))
      (node (ref "J2") (pin "7") (pinfunction "7_7") (pintype "passive"))
      (node (ref "J2") (pin "8") (pinfunction "8_8") (pintype "passive"))
      (node (ref "J2") (pin "9") (pinfunction "9_9") (pintype "passive"))
      (node (ref "R35") (pin "1") (pinfunction "1_1") (pintype "passive"))
      (node (ref "R36") (pin "1") (pinfunction "1_1") (pintype "passive"))
      (node (ref "R39") (pin "2") (pinfunction "2_2") (pintype "passive"))
      (node (ref "R41") (pin "1") (pinfunction "1_1") (pintype "passive"))
      (node (ref "R45") (pin "2") (pinfunction "2_2") (pintype "passive"))
      (node (ref "R53") (pin "1") (pinfunction "1_1") (pintype "passive"))
      (node (ref "R54") (pin "1") (pinfunction "1_1") (pintype "passive"))
      (node (ref "R57") (pin "2") (pinfunction "2_2") (pintype "passive"))
      (node (ref "R58") (pin "2") (pinfunction "2_2") (pintype "passive"))
      (node (ref "R59") (pin "1") (pinfunction "1_1") (pintype "passive"))
      (node (ref "R60") (pin "1") (pinfunction "1_1") (pintype "passive"))
      (node (ref "U2") (pin "4") (pinfunction "AGND_4") (pintype "passive"))
      (node (ref "U2") (pin "8") (pinfunction "PGND_8") (pintype "passive"))
      (node (ref "U3") (pin "15") (pinfunction "PWPD_15") (pintype "passive"))
      (node (ref "U3") (pin "5") (pinfunction "GND_5") (pintype "passive"))
      (node (ref "U3") (pin "8") (pinfunction "PGND_8") (pintype "passive"))
      (node (ref "U3") (pin "9") (pinfunction "PGND_9") (pintype "passive"))
      (node (ref "U4") (pin "3") (pinfunction "3_3") (pintype "passive"))
      (node (ref "U5") (pin "2") (pinfunction "Vee_2") (pintype "passive"))
      (node (ref "U6") (pin "2") (pinfunction "Vee_2") (pintype "passive"))
    )
    (net (code "17") (name "Net-(C28-Pad2)") (class "Default")
      (node (ref "C28") (pin "2") (pinfunction "2_2") (pintype "passive"))
      (node (ref "FB1") (pin "1") (pinfunction "1_1") (pintype "passive"))
      (node (ref "R40") (pin "1") (pinfunction "1_1") (pintype "passive"))
    )
    (net (code "18") (name "Net-(C29-Pad2)") (class "Default")
      (node (ref "C29") (pin "2") (pinfunction "2_2") (pintype "passive"))
      (node (ref "FB1") (pin "2") (pinfunction "2_2") (pintype "passive"))
      (node (ref "R43") (pin "1") (pinfunction "1_1") (pintype "passive"))
      (node (ref "TP7") (pin "1") (pinfunction "1_1") (pintype "passive"))
    )
    (net (code "19") (name "Net-(C34-Pad2)") (class "Default")
      (node (ref "C34") (pin "2") (pinfunction "2_2") (pintype "passive"))
      (node (ref "C35") (pin "2") (pinfunction "2_2") (pintype "passive"))
      (node (ref "F6") (pin "1") (pinfunction "1_1") (pintype "passive"))
      (node (ref "L5") (pin "2") (pinfunction "2_2") (pintype "passive"))
    )
    (net (code "20") (name "Net-(C36-Pad2)") (class "Default")
      (node (ref "C36") (pin "2") (pinfunction "2_2") (pintype "passive"))
      (node (ref "FB2") (pin "1") (pinfunction "1_1") (pintype "passive"))
      (node (ref "R48") (pin "1") (pinfunction "1_1") (pintype "passive"))
    )
    (net (code "21") (name "Net-(C42-Pad1)") (class "Default")
      (node (ref "C42") (pin "1") (pinfunction "1_1") (pintype "passive"))
      (node (ref "C43") (pin "1") (pinfunction "1_1") (pintype "passive"))
      (node (ref "FB3") (pin "2") (pinfunction "2_2") (pintype "passive"))
      (node (ref "R45") (pin "1") (pinfunction "1_1") (pintype "passive"))
    )
    (net (code "22") (name "Net-(C44-Pad1)") (class "Default")
      (node (ref "C44") (pin "1") (pinfunction "1_1") (pintype "passive"))
      (node (ref "R51") (pin "1") (pinfunction "1_1") (pintype "passive"))
      (node (ref "R53") (pin "2") (pinfunction "2_2") (pintype "passive"))
      (node (ref "TP18") (pin "1") (pinfunction "1_1") (pintype "passive"))
    )
    (net (code "23") (name "Net-(C45-Pad1)") (class "Default")
      (node (ref "C45") (pin "1") (pinfunction "1_1") (pintype "passive"))
      (node (ref "R52") (pin "1") (pinfunction "1_1") (pintype "passive"))
      (node (ref "R54") (pin "2") (pinfunction "2_2") (pintype "passive"))
      (node (ref "TP17") (pin "1") (pinfunction "1_1") (pintype "passive"))
    )
    (net (code "24") (name "Net-(D1-ANODE)") (class "Default")
      (node (ref "D1") (pin "1") (pinfunction "ANODE_1") (pintype "passive"))
      (node (ref "R33") (pin "1") (pinfunction "1_1") (pintype "passive"))
    )
    (net (code "25") (name "Net-(D2-Pad2)") (class "Default")
      (node (ref "D2") (pin "2") (pinfunction "2_2") (pintype "passive"))
      (node (ref "R32") (pin "1") (pinfunction "1_1") (pintype "passive"))
      (node (ref "R34") (pin "1") (pinfunction "1_1") (pintype "passive"))
      (node (ref "R35") (pin "2") (pinfunction "2_2") (pintype "passive"))
    )
    (net (code "26") (name "Net-(F6-Pad2)") (class "Default")
      (node (ref "F6") (pin "2") (pinfunction "2_2") (pintype "passive"))
      (node (ref "TP8") (pin "1") (pinfunction "1_1") (pintype "passive"))
    )
    (net (code "27") (name "Net-(J1-Pad1)") (class "Default")
      (node (ref "J1") (pin "1") (pinfunction "1_1") (pintype "passive"))
      (node (ref "J2") (pin "1") (pinfunction "1_1") (pintype "passive"))
    )
    (net (code "28") (name "Net-(J3-Pad1)") (class "Default")
      (node (ref "J3") (pin "1") (pinfunction "1_1") (pintype "passive"))
      (node (ref "R32") (pin "2") (pinfunction "2_2") (pintype "passive"))
    )
    (net (code "29") (name "Net-(R31-Pad1)") (class "Default")
      (node (ref "R31") (pin "1") (pinfunction "1_1") (pintype "passive"))
      (node (ref "R38") (pin "1") (pinfunction "1_1") (pintype "passive"))
    )
    (net (code "30") (name "Net-(R57-Pad1)") (class "Default")
      (node (ref "R57") (pin "1") (pinfunction "1_1") (pintype "passive"))
      (node (ref "TP21") (pin "1") (pinfunction "1_1") (pintype "passive"))
    )
    (net (code "31") (name "Net-(R58-Pad1)") (class "Default")
      (node (ref "R58") (pin "1") (pinfunction "1_1") (pintype "passive"))
      (node (ref "TP22") (pin "1") (pinfunction "1_1") (pintype "passive"))
    )
    (net (code "32") (name "Net-(U2-EN)") (class "Default")
      (node (ref "R34") (pin "2") (pinfunction "2_2") (pintype "passive"))
      (node (ref "U2") (pin "3") (pinfunction "EN_3") (pintype "passive"))
    )
    (net (code "33") (name "Net-(U2-FB)") (class "Default")
      (node (ref "R31") (pin "2") (pinfunction "2_2") (pintype "passive"))
      (node (ref "R36") (pin "2") (pinfunction "2_2") (pintype "passive"))
      (node (ref "U2") (pin "5") (pinfunction "FB_5") (pintype "passive"))
    )
    (net (code "34") (name "Net-(U2-SS{slash}TRK)") (class "Default")
      (node (ref "C51") (pin "2") (pinfunction "2_2") (pintype "passive"))
      (node (ref "U2") (pin "6") (pinfunction "SS/TRK_6") (pintype "passive"))
    )
    (net (code "35") (name "Net-(U2-SYNC)") (class "Default")
      (node (ref "R41") (pin "2") (pinfunction "2_2") (pintype "passive"))
      (node (ref "U2") (pin "2") (pinfunction "SYNC_2") (pintype "passive"))
    )
    (net (code "36") (name "Net-(U3-EN)") (class "Default")
      (node (ref "R44") (pin "2") (pinfunction "2_2") (pintype "passive"))
      (node (ref "U3") (pin "7") (pinfunction "EN_7") (pintype "passive"))
    )
    (net (code "37") (name "Net-(U3-PG)") (class "Default")
      (node (ref "C40") (pin "2") (pinfunction "2_2") (pintype "passive"))
      (node (ref "R47") (pin "1") (pinfunction "1_1") (pintype "passive"))
      (node (ref "U3") (pin "6") (pinfunction "PG_6") (pintype "passive"))
    )
    (net (code "38") (name "Net-(U3-SS)") (class "Default")
      (node (ref "C41") (pin "1") (pinfunction "1_1") (pintype "passive"))
      (node (ref "U3") (pin "4") (pinfunction "SS_4") (pintype "passive"))
    )
    (net (code "39") (name "Net-(U3-SW1)") (class "Default")
      (node (ref "C30") (pin "2") (pinfunction "2_2") (pintype "passive"))
      (node (ref "L5") (pin "1") (pinfunction "1_1") (pintype "passive"))
      (node (ref "U3") (pin "10") (pinfunction "SW1_10") (pintype "passive"))
      (node (ref "U3") (pin "11") (pinfunction "SW2_11") (pintype "passive"))
    )
    (net (code "40") (name "Net-(U3-V0)") (class "Default")
      (node (ref "C27") (pin "1") (pinfunction "1_1") (pintype "passive"))
      (node (ref "R42") (pin "1") (pinfunction "1_1") (pintype "passive"))
      (node (ref "U3") (pin "1") (pinfunction "V0_1") (pintype "passive"))
    )
    (net (code "41") (name "Net-(U3-VBST)") (class "Default")
      (node (ref "C30") (pin "1") (pinfunction "1_1") (pintype "passive"))
      (node (ref "U3") (pin "12") (pinfunction "VBST_12") (pintype "passive"))
    )
    (net (code "42") (name "Net-(U3-VREG)") (class "Default")
      (node (ref "R47") (pin "2") (pinfunction "2_2") (pintype "passive"))
      (node (ref "U3") (pin "3") (pinfunction "VREG_3") (pintype "passive"))
    )
    (net (code "43") (name "unconnected-(J2-Pad2)") (class "Default")
      (node (ref "J2") (pin "2") (pinfunction "2_2") (pintype "passive+no_connect"))
    )
    (net (code "44") (name "unconnected-(J2-Pad3)") (class "Default")
      (node (ref "J2") (pin "3") (pinfunction "3_3") (pintype "passive+no_connect"))
    )
  )
)
